# extBoard_sheet2_acc.net
KiCad netlist of a schematic drawn in Altium Designer
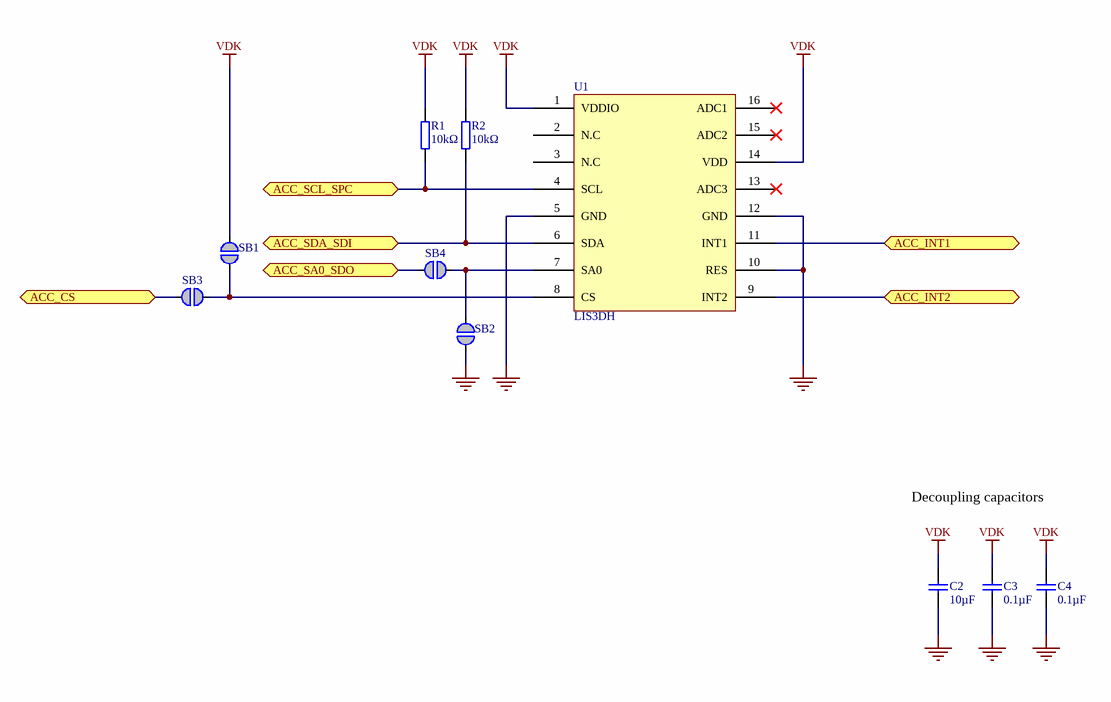
[diagram p0: extBoard_sheet2_acc.SchDoc]

(export (version "E")
  (design (tool "Eeschema 10.0.6"))
  (components
    (comp (ref "C2")
      (value "10µF")
      (footprint "CAPC2012X11L")
      (description "Capacitor, X5R, ±10%")
      (fields (field (name "PART NUMBER") "C0805-4µ7") (field (name "PUBLISHER") "Nordic Semiconductor"))
      (libsource (lib "pca10056") (part "CAP_0805"))
    )
    (comp (ref "C3")
      (value "0.1µF")
      (footprint "CAPC2012X11L")
      (description "Capacitor, X5R, ±10%")
      (fields (field (name "PART NUMBER") "C0805-4µ7") (field (name "PUBLISHER") "Nordic Semiconductor"))
      (libsource (lib "pca10056") (part "CAP_0805"))
    )
    (comp (ref "C4")
      (value "0.1µF")
      (footprint "CAPC2012X11L")
      (description "Capacitor, X5R, ±10%")
      (fields (field (name "PART NUMBER") "C0805-4µ7") (field (name "PUBLISHER") "Nordic Semiconductor"))
      (libsource (lib "pca10056") (part "CAP_0805"))
    )
    (comp (ref "R1") (value "10kΩ") (footprint "R0805") (libsource (lib "extBoardLib") (part "R0805")))
    (comp (ref "R2") (value "10kΩ") (footprint "R0805") (libsource (lib "extBoardLib") (part "R0805")))
    (comp (ref "SB1")
      (value "Solderbridge")
      (footprint "Solderbridge")
      (fields (field (name "PUBLISHER") "Nordic Semiconductor"))
      (libsource (lib "pca10056") (part "SOLDERBRIDGE"))
    )
    (comp (ref "SB2")
      (value "Solderbridge")
      (footprint "Solderbridge")
      (fields (field (name "PUBLISHER") "Nordic Semiconductor"))
      (libsource (lib "pca10056") (part "SOLDERBRIDGE"))
    )
    (comp (ref "SB3")
      (value "Solderbridge")
      (footprint "Solderbridge")
      (fields (field (name "PUBLISHER") "Nordic Semiconductor"))
      (libsource (lib "pca10056") (part "SOLDERBRIDGE"))
    )
    (comp (ref "SB4")
      (value "Solderbridge")
      (footprint "Solderbridge")
      (fields (field (name "PUBLISHER") "Nordic Semiconductor"))
      (libsource (lib "pca10056") (part "SOLDERBRIDGE"))
    )
    (comp (ref "U1")
      (value "LIS3DH")
      (footprint "LGA-16 (3x3x1.0mm)")
      (libsource (lib "extBoardLib") (part "LIS3DH"))
    )
  )
  (nets
    (net (code "1") (name "/ACC_CS") (class "Default")
      (node (ref "SB3") (pin "2") (pinfunction "1_2") (pintype "passive"))
    )
    (net (code "2") (name "/ACC_INT1") (class "Default")
      (node (ref "U1") (pin "11") (pinfunction "INT1_11") (pintype "passive"))
    )
    (net (code "3") (name "/ACC_INT2") (class "Default")
      (node (ref "U1") (pin "9") (pinfunction "INT2_9") (pintype "passive"))
    )
    (net (code "4") (name "/ACC_SA0_SDO") (class "Default")
      (node (ref "SB4") (pin "1") (pinfunction "0_1") (pintype "passive"))
    )
    (net (code "5") (name "/ACC_SCL_SPC") (class "Default")
      (node (ref "R1") (pin "1") (pinfunction "1_1") (pintype "passive"))
      (node (ref "U1") (pin "4") (pinfunction "SCL_4") (pintype "passive"))
    )
    (net (code "6") (name "/ACC_SDA_SDI") (class "Default")
      (node (ref "R2") (pin "1") (pinfunction "1_1") (pintype "passive"))
      (node (ref "U1") (pin "6") (pinfunction "SDA_6") (pintype "passive"))
    )
    (net (code "7") (name "GND") (class "Default")
      (node (ref "C2") (pin "1") (pinfunction "1_1") (pintype "passive"))
      (node (ref "C3") (pin "1") (pinfunction "1_1") (pintype "passive"))
      (node (ref "C4") (pin "1") (pinfunction "1_1") (pintype "passive"))
      (node (ref "SB2") (pin "2") (pinfunction "1_2") (pintype "passive"))
      (node (ref "U1") (pin "10") (pinfunction "RES_10") (pintype "passive"))
      (node (ref "U1") (pin "12") (pinfunction "GND_12") (pintype "passive"))
      (node (ref "U1") (pin "5") (pinfunction "GND_5") (pintype "passive"))
    )
    (net (code "8") (name "Net-(SB1-1)") (class "Default")
      (node (ref "SB1") (pin "2") (pinfunction "1_2") (pintype "passive"))
      (node (ref "SB3") (pin "1") (pinfunction "0_1") (pintype "passive"))
      (node (ref "U1") (pin "8") (pinfunction "CS_8") (pintype "passive"))
    )
    (net (code "9") (name "Net-(SB2-0)") (class "Default")
      (node (ref "SB2") (pin "1") (pinfunction "0_1") (pintype "passive"))
      (node (ref "SB4") (pin "2") (pinfunction "1_2") (pintype "passive"))
      (node (ref "U1") (pin "7") (pinfunction "SA0_7") (pintype "passive"))
    )
    (net (code "10") (name "VDK") (class "Default")
      (node (ref "C2") (pin "2") (pinfunction "2_2") (pintype "passive"))
      (node (ref "C3") (pin "2") (pinfunction "2_2") (pintype "passive"))
      (node (ref "C4") (pin "2") (pinfunction "2_2") (pintype "passive"))
      (node (ref "R1") (pin "2") (pinfunction "2_2") (pintype "passive"))
      (node (ref "R2") (pin "2") (pinfunction "2_2") (pintype "passive"))
      (node (ref "SB1") (pin "1") (pinfunction "0_1") (pintype "passive"))
      (node (ref "U1") (pin "1") (pinfunction "VDDIO_1") (pintype "passive"))
      (node (ref "U1") (pin "14") (pinfunction "VDD_14") (pintype "passive"))
    )
    (net (code "11") (name "unconnected-(U1-ADC1-Pad16)") (class "Default")
      (node (ref "U1") (pin "16") (pinfunction "ADC1_16") (pintype "passive+no_connect"))
    )
    (net (code "12") (name "unconnected-(U1-ADC2-Pad15)") (class "Default")
      (node (ref "U1") (pin "15") (pinfunction "ADC2_15") (pintype "passive+no_connect"))
    )
    (net (code "13") (name "unconnected-(U1-ADC3-Pad13)") (class "Default")
      (node (ref "U1") (pin "13") (pinfunction "ADC3_13") (pintype "passive+no_connect"))
    )
    (net (code "14") (name "unconnected-(U1-N.C-Pad2)") (class "Default")
      (node (ref "U1") (pin "2") (pinfunction "N.C_2") (pintype "passive"))
    )
    (net (code "15") (name "unconnected-(U1-N.C-Pad3)") (class "Default")
      (node (ref "U1") (pin "3") (pinfunction "N.C_3") (pintype "passive"))
    )
  )
)
